# multiline_sensor.net
KiCad netlist of a schematic drawn in EAGLE
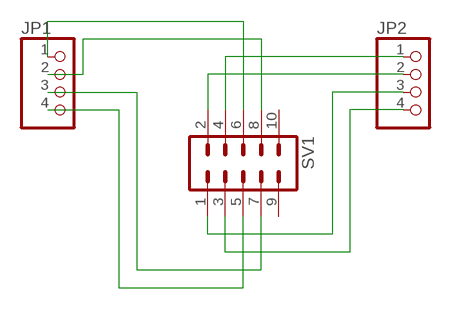
[diagram p0: schematic, sheet 1]

(export (version "E")
  (design (tool "Eeschema 10.0.6"))
  (components
    (comp (ref "JP1")
      (value "PINHD-1X4")
      (footprint "eagle-import:1X04")
      (libsource (lib "eagle-import") (part "PINHD-1X4"))
    )
    (comp (ref "JP2")
      (value "PINHD-1X4")
      (footprint "eagle-import:1X04")
      (libsource (lib "eagle-import") (part "PINHD-1X4"))
    )
    (comp (ref "SV1")
      (value "ML10")
      (footprint "eagle-import:ML10")
      (libsource (lib "eagle-import") (part "ML10"))
    )
  )
  (nets
    (net (code "1") (name "Net-(JP1-Pad1)") (class "Default")
      (node (ref "JP1") (pin "1") (pinfunction "1_1") (pintype "passive"))
      (node (ref "SV1") (pin "6") (pinfunction "6_6") (pintype "passive"))
    )
    (net (code "2") (name "Net-(JP1-Pad2)") (class "Default")
      (node (ref "JP1") (pin "2") (pinfunction "2_2") (pintype "passive"))
      (node (ref "SV1") (pin "8") (pinfunction "8_8") (pintype "passive"))
    )
    (net (code "3") (name "Net-(JP1-Pad3)") (class "Default")
      (node (ref "JP1") (pin "3") (pinfunction "3_3") (pintype "passive"))
      (node (ref "SV1") (pin "7") (pinfunction "7_7") (pintype "passive"))
    )
    (net (code "4") (name "Net-(JP1-Pad4)") (class "Default")
      (node (ref "JP1") (pin "4") (pinfunction "4_4") (pintype "passive"))
      (node (ref "SV1") (pin "5") (pinfunction "5_5") (pintype "passive"))
    )
    (net (code "5") (name "Net-(JP2-Pad1)") (class "Default")
      (node (ref "JP2") (pin "1") (pinfunction "1_1") (pintype "passive"))
      (node (ref "SV1") (pin "4") (pinfunction "4_4") (pintype "passive"))
    )
    (net (code "6") (name "Net-(JP2-Pad2)") (class "Default")
      (node (ref "JP2") (pin "2") (pinfunction "2_2") (pintype "passive"))
      (node (ref "SV1") (pin "2") (pinfunction "2_2") (pintype "passive"))
    )
    (net (code "7") (name "Net-(JP2-Pad3)") (class "Default")
      (node (ref "JP2") (pin "3") (pinfunction "3_3") (pintype "passive"))
      (node (ref "SV1") (pin "1") (pinfunction "1_1") (pintype "passive"))
    )
    (net (code "8") (name "Net-(JP2-Pad4)") (class "Default")
      (node (ref "JP2") (pin "4") (pinfunction "4_4") (pintype "passive"))
      (node (ref "SV1") (pin "3") (pinfunction "3_3") (pintype "passive"))
    )
    (net (code "9") (name "unconnected-(SV1-Pad9)") (class "Default")
      (node (ref "SV1") (pin "9") (pinfunction "9_9") (pintype "passive"))
    )
    (net (code "10") (name "unconnected-(SV1-Pad10)") (class "Default")
      (node (ref "SV1") (pin "10") (pinfunction "10_10") (pintype "passive"))
    )
  )
)
